# growPi_v2_1.net
KiCad netlist of a schematic drawn in EAGLE
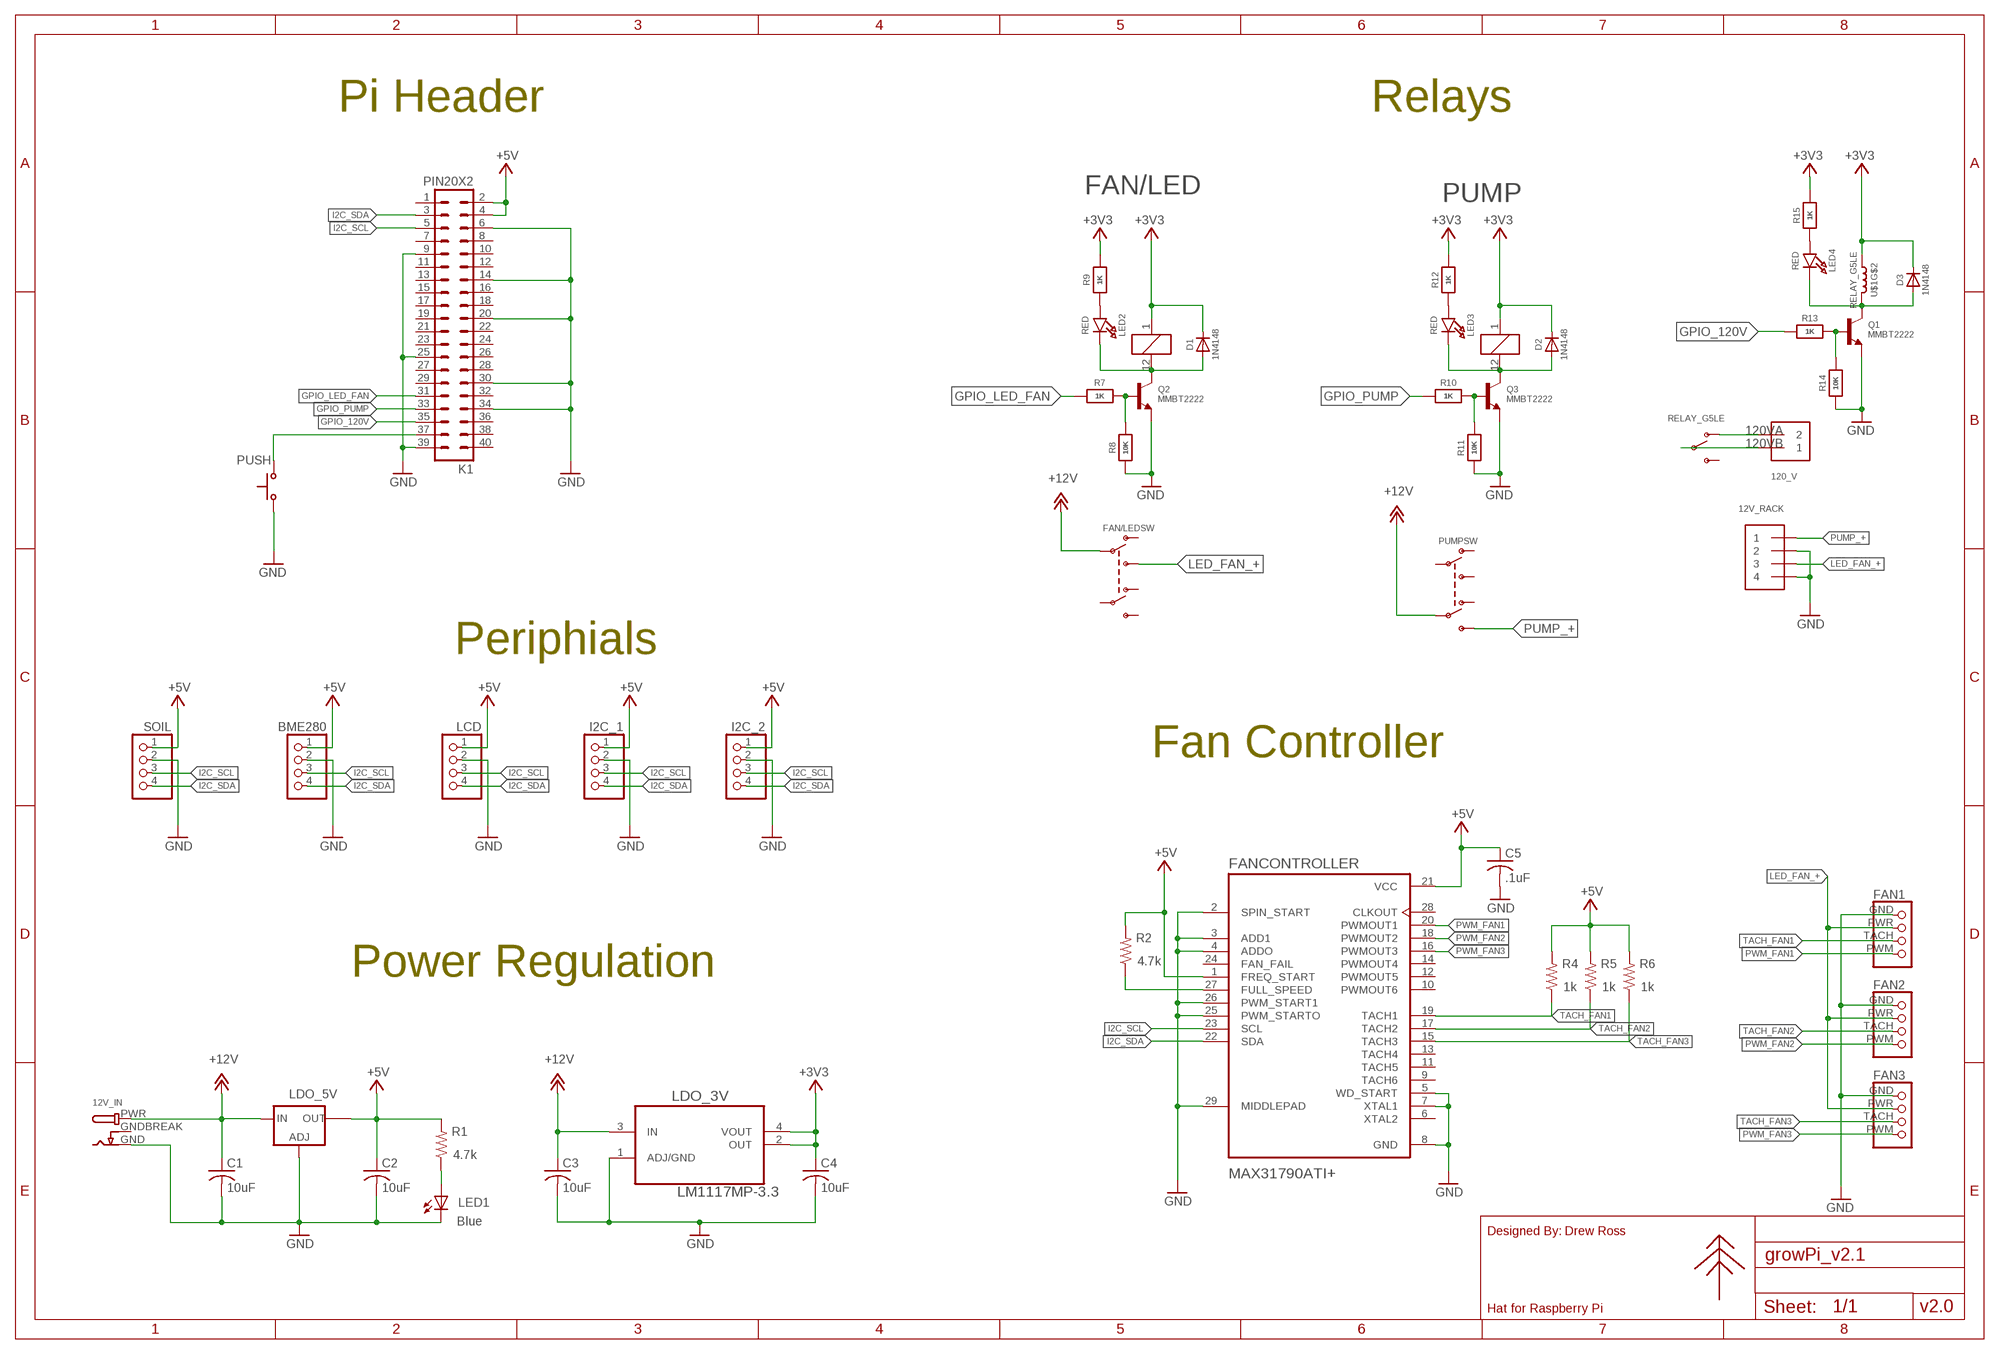
[diagram p0: schematic, sheet 1]

(export (version "E")
  (design (tool "Eeschema 10.0.6"))
  (components
    (comp (ref "12V_IN")
      (value "DCBARRELSMT_CORRECT")
      (footprint "eagle-import:DCJACK_2MM_SMT")
      (libsource (lib "eagle-import") (part "DCBARRELSMT_CORRECT"))
    )
    (comp (ref "12V_RACK")
      (value "TERMBLOCK_1X4-5.0MM")
      (footprint "eagle-import:TERMBLOCK_1X4-5.0MM")
      (libsource (lib "eagle-import") (part "TERMBLOCK_1X4-5.0MM"))
    )
    (comp (ref "120_V")
      (value "TERMBLOCK_1X2-5.0MM")
      (footprint "eagle-import:TERMBLOCK_1X2-5.0MM")
      (libsource (lib "eagle-import") (part "TERMBLOCK_1X2-5.0MM"))
    )
    (comp (ref "BME280")
      (value "PINHD-1X4")
      (footprint "eagle-import:1X04")
      (libsource (lib "eagle-import") (part "PINHD-1X4"))
    )
    (comp (ref "C1")
      (value "10uF")
      (footprint "eagle-import:C0603")
      (libsource (lib "eagle-import") (part "C-USC0603"))
    )
    (comp (ref "C2")
      (value "10uF")
      (footprint "eagle-import:C0603")
      (libsource (lib "eagle-import") (part "C-USC0603"))
    )
    (comp (ref "C3")
      (value "10uF")
      (footprint "eagle-import:C0603")
      (libsource (lib "eagle-import") (part "C-USC0603"))
    )
    (comp (ref "C4")
      (value "10uF")
      (footprint "eagle-import:C0603")
      (libsource (lib "eagle-import") (part "C-USC0603"))
    )
    (comp (ref "C5")
      (value ".1uF")
      (footprint "eagle-import:C0603")
      (libsource (lib "eagle-import") (part "C-USC0603"))
    )
    (comp (ref "D1")
      (value "1N4148")
      (footprint "eagle-import:SOD-323")
      (libsource (lib "eagle-import") (part "DIODESOD-323"))
    )
    (comp (ref "D2")
      (value "1N4148")
      (footprint "eagle-import:SOD-323")
      (libsource (lib "eagle-import") (part "DIODESOD-323"))
    )
    (comp (ref "D3")
      (value "1N4148")
      (footprint "eagle-import:SOD-323")
      (libsource (lib "eagle-import") (part "DIODESOD-323"))
    )
    (comp (ref "FAN/LED")
      (value "RELAY_NONLATCHING-EE2NUH")
      (footprint "eagle-import:RELAY_EE2_NOLATCH")
      (libsource (lib "eagle-import") (part "RELAY_NONLATCHING-EE2NUH"))
    )
    (comp (ref "FAN1")
      (value "4PIN-MOLEX-FAN")
      (footprint "eagle-import:4PIN-FAN-HEADER")
      (libsource (lib "eagle-import") (part "4PIN-MOLEX-FAN"))
    )
    (comp (ref "FAN2")
      (value "4PIN-MOLEX-FAN")
      (footprint "eagle-import:4PIN-FAN-HEADER")
      (libsource (lib "eagle-import") (part "4PIN-MOLEX-FAN"))
    )
    (comp (ref "FAN3")
      (value "4PIN-MOLEX-FAN")
      (footprint "eagle-import:4PIN-FAN-HEADER")
      (libsource (lib "eagle-import") (part "4PIN-MOLEX-FAN"))
    )
    (comp (ref "FANCONTROLLER")
      (value "MAX31790ATI+")
      (footprint "eagle-import:QFN40P400X400X80-29N")
      (fields (field (name "MF") "Maxim Integrated"))
      (libsource (lib "eagle-import") (part "MAX31790ATI+"))
    )
    (comp (ref "I2C_1")
      (value "PINHD-1X4")
      (footprint "eagle-import:1X04")
      (libsource (lib "eagle-import") (part "PINHD-1X4"))
    )
    (comp (ref "I2C_2")
      (value "PINHD-1X4")
      (footprint "eagle-import:1X04")
      (libsource (lib "eagle-import") (part "PINHD-1X4"))
    )
    (comp (ref "K1")
      (value "PIN20X2")
      (footprint "eagle-import:PIN_20X2")
      (libsource (lib "eagle-import") (part "PIN20X2"))
    )
    (comp (ref "LCD")
      (value "PINHD-1X4")
      (footprint "eagle-import:1X04")
      (libsource (lib "eagle-import") (part "PINHD-1X4"))
    )
    (comp (ref "LDO_3V")
      (value "LM1117MP-3.3")
      (footprint "eagle-import:SOT230P696X180-4N")
      (fields (field (name "MF") "Texas Instruments"))
      (libsource (lib "eagle-import") (part "LM1117MP-3.3"))
    )
    (comp (ref "LDO_5V")
      (value "LM1084IS")
      (footprint "eagle-import:TO263")
      (libsource (lib "eagle-import") (part "LM1084IS"))
    )
    (comp (ref "LED1")
      (value "Blue")
      (footprint "eagle-import:CHIPLED_0603")
      (libsource (lib "eagle-import") (part "LEDCHIPLED_0603"))
    )
    (comp (ref "LED2")
      (value "RED")
      (footprint "eagle-import:CHIPLED_0603_NOOUTLINE")
      (libsource (lib "eagle-import") (part "LED0603_NOOUTLINE"))
    )
    (comp (ref "LED3")
      (value "RED")
      (footprint "eagle-import:CHIPLED_0603_NOOUTLINE")
      (libsource (lib "eagle-import") (part "LED0603_NOOUTLINE"))
    )
    (comp (ref "LED4")
      (value "RED")
      (footprint "eagle-import:CHIPLED_0603_NOOUTLINE")
      (libsource (lib "eagle-import") (part "LED0603_NOOUTLINE"))
    )
    (comp (ref "PLANTLOGO")
      (value "PLANTLOGO")
      (footprint "eagle-import:PLANT")
      (libsource (lib "eagle-import") (part "PLANTLOGO"))
    )
    (comp (ref "PUMP")
      (value "RELAY_NONLATCHING-EE2NUH")
      (footprint "eagle-import:RELAY_EE2_NOLATCH")
      (libsource (lib "eagle-import") (part "RELAY_NONLATCHING-EE2NUH"))
    )
    (comp (ref "PUSH")
      (value "PTS645SSMTR")
      (footprint "eagle-import:PTS645-SMD")
      (libsource (lib "eagle-import") (part "PTS645S???SMTR"))
    )
    (comp (ref "Q1")
      (value "MMBT2222")
      (footprint "eagle-import:SOT23-R")
      (libsource (lib "eagle-import") (part "TRANSISTOR_NPN"))
    )
    (comp (ref "Q2")
      (value "MMBT2222")
      (footprint "eagle-import:SOT23-R")
      (libsource (lib "eagle-import") (part "TRANSISTOR_NPN"))
    )
    (comp (ref "Q3")
      (value "MMBT2222")
      (footprint "eagle-import:SOT23-R")
      (libsource (lib "eagle-import") (part "TRANSISTOR_NPN"))
    )
    (comp (ref "R1")
      (value "4.7k")
      (footprint "eagle-import:R0603")
      (libsource (lib "eagle-import") (part "R-US_R0603"))
    )
    (comp (ref "R2")
      (value "4.7k")
      (footprint "eagle-import:R0603")
      (libsource (lib "eagle-import") (part "R-US_R0603"))
    )
    (comp (ref "R4")
      (value "1k")
      (footprint "eagle-import:R0603")
      (libsource (lib "eagle-import") (part "R-US_R0603"))
    )
    (comp (ref "R5")
      (value "1k")
      (footprint "eagle-import:R0603")
      (libsource (lib "eagle-import") (part "R-US_R0603"))
    )
    (comp (ref "R6")
      (value "1k")
      (footprint "eagle-import:R0603")
      (libsource (lib "eagle-import") (part "R-US_R0603"))
    )
    (comp (ref "R7")
      (value "1K")
      (footprint "eagle-import:0603-NO")
      (libsource (lib "eagle-import") (part "RESISTOR_0603_NOOUT"))
    )
    (comp (ref "R8")
      (value "10K")
      (footprint "eagle-import:0603-NO")
      (libsource (lib "eagle-import") (part "RESISTOR_0603_NOOUT"))
    )
    (comp (ref "R9")
      (value "1K")
      (footprint "eagle-import:0603-NO")
      (libsource (lib "eagle-import") (part "RESISTOR_0603_NOOUT"))
    )
    (comp (ref "R10")
      (value "1K")
      (footprint "eagle-import:0603-NO")
      (libsource (lib "eagle-import") (part "RESISTOR_0603_NOOUT"))
    )
    (comp (ref "R11")
      (value "10K")
      (footprint "eagle-import:0603-NO")
      (libsource (lib "eagle-import") (part "RESISTOR_0603_NOOUT"))
    )
    (comp (ref "R12")
      (value "1K")
      (footprint "eagle-import:0603-NO")
      (libsource (lib "eagle-import") (part "RESISTOR_0603_NOOUT"))
    )
    (comp (ref "R13")
      (value "1K")
      (footprint "eagle-import:0603-NO")
      (libsource (lib "eagle-import") (part "RESISTOR_0603_NOOUT"))
    )
    (comp (ref "R14")
      (value "10K")
      (footprint "eagle-import:0603-NO")
      (libsource (lib "eagle-import") (part "RESISTOR_0603_NOOUT"))
    )
    (comp (ref "R15")
      (value "1K")
      (footprint "eagle-import:0603-NO")
      (libsource (lib "eagle-import") (part "RESISTOR_0603_NOOUT"))
    )
    (comp (ref "SOIL")
      (value "PINHD-1X4")
      (footprint "eagle-import:1X04")
      (libsource (lib "eagle-import") (part "PINHD-1X4"))
    )
    (comp (ref "U$1")
      (value "RELAY_G5LE")
      (footprint "eagle-import:RELAY_G5LE-1")
      (libsource (lib "eagle-import") (part "RELAY_G5LE"))
    )
  )
  (nets
    (net (code "1") (name "+3V3") (class "Default")
      (node (ref "C4") (pin "1") (pinfunction "1_1") (pintype "passive"))
      (node (ref "D1") (pin "C") (pinfunction "C_C") (pintype "passive"))
      (node (ref "D2") (pin "C") (pinfunction "C_C") (pintype "passive"))
      (node (ref "D3") (pin "C") (pinfunction "C_C") (pintype "passive"))
      (node (ref "FAN/LED") (pin "1") (pinfunction "1_1") (pintype "passive"))
      (node (ref "LDO_3V") (pin "2") (pinfunction "OUT_2") (pintype "output"))
      (node (ref "LDO_3V") (pin "4") (pinfunction "VOUT_4") (pintype "output"))
      (node (ref "PUMP") (pin "1") (pinfunction "1_1") (pintype "passive"))
      (node (ref "R12") (pin "2") (pinfunction "2_2") (pintype "passive"))
      (node (ref "R15") (pin "2") (pinfunction "2_2") (pintype "passive"))
      (node (ref "R9") (pin "2") (pinfunction "2_2") (pintype "passive"))
      (node (ref "U$1") (pin "2") (pinfunction "1_2") (pintype "passive"))
    )
    (net (code "2") (name "+5V") (class "Default")
      (node (ref "BME280") (pin "1") (pinfunction "1_1") (pintype "passive"))
      (node (ref "C2") (pin "1") (pinfunction "1_1") (pintype "passive"))
      (node (ref "C5") (pin "1") (pinfunction "1_1") (pintype "passive"))
      (node (ref "FANCONTROLLER") (pin "1") (pinfunction "FREQ_START_1") (pintype "bidirectional"))
      (node (ref "FANCONTROLLER") (pin "21") (pinfunction "VCC_21") (pintype "power_in"))
      (node (ref "I2C_1") (pin "1") (pinfunction "1_1") (pintype "passive"))
      (node (ref "I2C_2") (pin "1") (pinfunction "1_1") (pintype "passive"))
      (node (ref "K1") (pin "2") (pinfunction "2_2") (pintype "passive"))
      (node (ref "K1") (pin "4") (pinfunction "4_4") (pintype "passive"))
      (node (ref "LCD") (pin "1") (pinfunction "1_1") (pintype "passive"))
      (node (ref "LDO_5V") (pin "2") (pinfunction "OUT_2") (pintype "passive"))
      (node (ref "R1") (pin "2") (pinfunction "2_2") (pintype "passive"))
      (node (ref "R2") (pin "2") (pinfunction "2_2") (pintype "passive"))
      (node (ref "R4") (pin "2") (pinfunction "2_2") (pintype "passive"))
      (node (ref "R5") (pin "2") (pinfunction "2_2") (pintype "passive"))
      (node (ref "R6") (pin "2") (pinfunction "2_2") (pintype "passive"))
      (node (ref "SOIL") (pin "1") (pinfunction "1_1") (pintype "passive"))
    )
    (net (code "3") (name "+12V") (class "Default")
      (node (ref "12V_IN") (pin "PWR") (pinfunction "PWR_PWR") (pintype "power_in"))
      (node (ref "C1") (pin "1") (pinfunction "1_1") (pintype "passive"))
      (node (ref "C3") (pin "1") (pinfunction "1_1") (pintype "passive"))
      (node (ref "FAN/LED") (pin "9") (pinfunction "P1_9") (pintype "passive"))
      (node (ref "LDO_3V") (pin "3") (pinfunction "IN_3") (pintype "input"))
      (node (ref "LDO_5V") (pin "3") (pinfunction "IN_3") (pintype "input"))
      (node (ref "PUMP") (pin "4") (pinfunction "P2_4") (pintype "passive"))
    )
    (net (code "4") (name "/120VA") (class "Default")
      (node (ref "120_V") (pin "2") (pinfunction "2_2") (pintype "passive"))
      (node (ref "U$1") (pin "3") (pinfunction "O_3") (pintype "passive"))
    )
    (net (code "5") (name "/120VB") (class "Default")
      (node (ref "120_V") (pin "1") (pinfunction "1_1") (pintype "passive"))
      (node (ref "U$1") (pin "1") (pinfunction "P_1") (pintype "passive"))
    )
    (net (code "6") (name "/GNDBREAK") (class "Default")
      (node (ref "12V_IN") (pin "GNDBREAK") (pinfunction "GNDBREAK_GNDBREAK") (pintype "power_in"))
    )
    (net (code "7") (name "GND") (class "Default")
      (node (ref "12V_IN") (pin "GND") (pinfunction "GND_GND") (pintype "power_in"))
      (node (ref "12V_RACK") (pin "2") (pinfunction "2_2") (pintype "passive"))
      (node (ref "12V_RACK") (pin "4") (pinfunction "4_4") (pintype "passive"))
      (node (ref "BME280") (pin "2") (pinfunction "2_2") (pintype "passive"))
      (node (ref "C1") (pin "2") (pinfunction "2_2") (pintype "passive"))
      (node (ref "C2") (pin "2") (pinfunction "2_2") (pintype "passive"))
      (node (ref "C3") (pin "2") (pinfunction "2_2") (pintype "passive"))
      (node (ref "C4") (pin "2") (pinfunction "2_2") (pintype "passive"))
      (node (ref "C5") (pin "2") (pinfunction "2_2") (pintype "passive"))
      (node (ref "FAN1") (pin "GND") (pinfunction "1_GND") (pintype "passive"))
      (node (ref "FAN2") (pin "GND") (pinfunction "1_GND") (pintype "passive"))
      (node (ref "FAN3") (pin "GND") (pinfunction "1_GND") (pintype "passive"))
      (node (ref "FANCONTROLLER") (pin "2") (pinfunction "SPIN_START_2") (pintype "input"))
      (node (ref "FANCONTROLLER") (pin "25") (pinfunction "PWM_STARTO_25") (pintype "bidirectional"))
      (node (ref "FANCONTROLLER") (pin "26") (pinfunction "PWM_START1_26") (pintype "bidirectional"))
      (node (ref "FANCONTROLLER") (pin "29") (pinfunction "MIDDLEPAD_29") (pintype "bidirectional"))
      (node (ref "FANCONTROLLER") (pin "3") (pinfunction "ADD1_3") (pintype "bidirectional"))
      (node (ref "FANCONTROLLER") (pin "4") (pinfunction "ADDO_4") (pintype "bidirectional"))
      (node (ref "FANCONTROLLER") (pin "5") (pinfunction "WD_START_5") (pintype "bidirectional"))
      (node (ref "FANCONTROLLER") (pin "7") (pinfunction "XTAL1_7") (pintype "bidirectional"))
      (node (ref "FANCONTROLLER") (pin "8") (pinfunction "GND_8") (pintype "power_in"))
      (node (ref "I2C_1") (pin "2") (pinfunction "2_2") (pintype "passive"))
      (node (ref "I2C_2") (pin "2") (pinfunction "2_2") (pintype "passive"))
      (node (ref "K1") (pin "14") (pinfunction "14_14") (pintype "passive"))
      (node (ref "K1") (pin "20") (pinfunction "20_20") (pintype "passive"))
      (node (ref "K1") (pin "25") (pinfunction "25_25") (pintype "passive"))
      (node (ref "K1") (pin "30") (pinfunction "30_30") (pintype "passive"))
      (node (ref "K1") (pin "34") (pinfunction "34_34") (pintype "passive"))
      (node (ref "K1") (pin "39") (pinfunction "39_39") (pintype "passive"))
      (node (ref "K1") (pin "6") (pinfunction "6_6") (pintype "passive"))
      (node (ref "K1") (pin "9") (pinfunction "9_9") (pintype "passive"))
      (node (ref "LCD") (pin "2") (pinfunction "2_2") (pintype "passive"))
      (node (ref "LDO_3V") (pin "1") (pinfunction "ADJ/GND_1") (pintype "passive"))
      (node (ref "LDO_5V") (pin "1") (pinfunction "ADJ_1") (pintype "input"))
      (node (ref "LED1") (pin "C") (pinfunction "C_C") (pintype "passive"))
      (node (ref "PUSH") (pin "1") (pinfunction "P_1") (pintype "passive"))
      (node (ref "PUSH") (pin "2") (pinfunction "P_2") (pintype "passive"))
      (node (ref "Q1") (pin "2") (pinfunction "E_2") (pintype "passive"))
      (node (ref "Q2") (pin "2") (pinfunction "E_2") (pintype "passive"))
      (node (ref "Q3") (pin "2") (pinfunction "E_2") (pintype "passive"))
      (node (ref "R11") (pin "1") (pinfunction "1_1") (pintype "passive"))
      (node (ref "R14") (pin "1") (pinfunction "1_1") (pintype "passive"))
      (node (ref "R8") (pin "1") (pinfunction "1_1") (pintype "passive"))
      (node (ref "SOIL") (pin "2") (pinfunction "2_2") (pintype "passive"))
    )
    (net (code "8") (name "GPIO_120V") (class "Default")
      (node (ref "K1") (pin "35") (pinfunction "35_35") (pintype "passive"))
      (node (ref "R13") (pin "1") (pinfunction "1_1") (pintype "passive"))
    )
    (net (code "9") (name "GPIO_LED_FAN") (class "Default")
      (node (ref "K1") (pin "31") (pinfunction "31_31") (pintype "passive"))
      (node (ref "R7") (pin "1") (pinfunction "1_1") (pintype "passive"))
    )
    (net (code "10") (name "GPIO_PUMP") (class "Default")
      (node (ref "K1") (pin "33") (pinfunction "33_33") (pintype "passive"))
      (node (ref "R10") (pin "1") (pinfunction "1_1") (pintype "passive"))
    )
    (net (code "11") (name "I2C_SCL") (class "Default")
      (node (ref "BME280") (pin "3") (pinfunction "3_3") (pintype "passive"))
      (node (ref "FANCONTROLLER") (pin "23") (pinfunction "SCL_23") (pintype "bidirectional"))
      (node (ref "I2C_1") (pin "3") (pinfunction "3_3") (pintype "passive"))
      (node (ref "I2C_2") (pin "3") (pinfunction "3_3") (pintype "passive"))
      (node (ref "K1") (pin "5") (pinfunction "5_5") (pintype "passive"))
      (node (ref "LCD") (pin "3") (pinfunction "3_3") (pintype "passive"))
      (node (ref "SOIL") (pin "3") (pinfunction "3_3") (pintype "passive"))
    )
    (net (code "12") (name "I2C_SDA") (class "Default")
      (node (ref "BME280") (pin "4") (pinfunction "4_4") (pintype "passive"))
      (node (ref "FANCONTROLLER") (pin "22") (pinfunction "SDA_22") (pintype "bidirectional"))
      (node (ref "I2C_1") (pin "4") (pinfunction "4_4") (pintype "passive"))
      (node (ref "I2C_2") (pin "4") (pinfunction "4_4") (pintype "passive"))
      (node (ref "K1") (pin "3") (pinfunction "3_3") (pintype "passive"))
      (node (ref "LCD") (pin "4") (pinfunction "4_4") (pintype "passive"))
      (node (ref "SOIL") (pin "4") (pinfunction "4_4") (pintype "passive"))
    )
    (net (code "13") (name "LED_FAN_+") (class "Default")
      (node (ref "12V_RACK") (pin "3") (pinfunction "3_3") (pintype "passive"))
      (node (ref "FAN/LED") (pin "8") (pinfunction "S1_8") (pintype "passive"))
      (node (ref "FAN1") (pin "PWR") (pinfunction "2_PWR") (pintype "passive"))
      (node (ref "FAN2") (pin "PWR") (pinfunction "2_PWR") (pintype "passive"))
      (node (ref "FAN3") (pin "PWR") (pinfunction "2_PWR") (pintype "passive"))
    )
    (net (code "14") (name "Net-(FAN/LEDA-2)") (class "Default")
      (node (ref "D1") (pin "A") (pinfunction "A_A") (pintype "passive"))
      (node (ref "FAN/LED") (pin "12") (pinfunction "2_12") (pintype "passive"))
      (node (ref "LED2") (pin "C") (pinfunction "C_C") (pintype "passive"))
      (node (ref "Q2") (pin "3") (pinfunction "C_3") (pintype "passive"))
    )
    (net (code "15") (name "Net-(FANCONTROLLER-FULL_SPEED)") (class "Default")
      (node (ref "FANCONTROLLER") (pin "27") (pinfunction "FULL_SPEED_27") (pintype "bidirectional"))
      (node (ref "R2") (pin "1") (pinfunction "1_1") (pintype "passive"))
    )
    (net (code "16") (name "Net-(K1-Pad37)") (class "Default")
      (node (ref "K1") (pin "37") (pinfunction "37_37") (pintype "passive"))
      (node (ref "PUSH") (pin "3") (pinfunction "S_3") (pintype "passive"))
      (node (ref "PUSH") (pin "4") (pinfunction "S_4") (pintype "passive"))
    )
    (net (code "17") (name "Net-(LED1-PadA)") (class "Default")
      (node (ref "LED1") (pin "A") (pinfunction "A_A") (pintype "passive"))
      (node (ref "R1") (pin "1") (pinfunction "1_1") (pintype "passive"))
    )
    (net (code "18") (name "Net-(LED2-PadA)") (class "Default")
      (node (ref "LED2") (pin "A") (pinfunction "A_A") (pintype "passive"))
      (node (ref "R9") (pin "1") (pinfunction "1_1") (pintype "passive"))
    )
    (net (code "19") (name "Net-(LED3-PadA)") (class "Default")
      (node (ref "LED3") (pin "A") (pinfunction "A_A") (pintype "passive"))
      (node (ref "R12") (pin "1") (pinfunction "1_1") (pintype "passive"))
    )
    (net (code "20") (name "Net-(LED4-PadA)") (class "Default")
      (node (ref "LED4") (pin "A") (pinfunction "A_A") (pintype "passive"))
      (node (ref "R15") (pin "1") (pinfunction "1_1") (pintype "passive"))
    )
    (net (code "21") (name "Net-(PUMPA-2)") (class "Default")
      (node (ref "D2") (pin "A") (pinfunction "A_A") (pintype "passive"))
      (node (ref "LED3") (pin "C") (pinfunction "C_C") (pintype "passive"))
      (node (ref "PUMP") (pin "12") (pinfunction "2_12") (pintype "passive"))
      (node (ref "Q3") (pin "3") (pinfunction "C_3") (pintype "passive"))
    )
    (net (code "22") (name "Net-(Q1-B)") (class "Default")
      (node (ref "Q1") (pin "1") (pinfunction "B_1") (pintype "passive"))
      (node (ref "R13") (pin "2") (pinfunction "2_2") (pintype "passive"))
      (node (ref "R14") (pin "2") (pinfunction "2_2") (pintype "passive"))
    )
    (net (code "23") (name "Net-(Q1-C)") (class "Default")
      (node (ref "D3") (pin "A") (pinfunction "A_A") (pintype "passive"))
      (node (ref "LED4") (pin "C") (pinfunction "C_C") (pintype "passive"))
      (node (ref "Q1") (pin "3") (pinfunction "C_3") (pintype "passive"))
      (node (ref "U$1") (pin "5") (pinfunction "2_5") (pintype "passive"))
    )
    (net (code "24") (name "Net-(Q2-B)") (class "Default")
      (node (ref "Q2") (pin "1") (pinfunction "B_1") (pintype "passive"))
      (node (ref "R7") (pin "2") (pinfunction "2_2") (pintype "passive"))
      (node (ref "R8") (pin "2") (pinfunction "2_2") (pintype "passive"))
    )
    (net (code "25") (name "Net-(Q3-B)") (class "Default")
      (node (ref "Q3") (pin "1") (pinfunction "B_1") (pintype "passive"))
      (node (ref "R10") (pin "2") (pinfunction "2_2") (pintype "passive"))
      (node (ref "R11") (pin "2") (pinfunction "2_2") (pintype "passive"))
    )
    (net (code "26") (name "PUMP_+") (class "Default")
      (node (ref "12V_RACK") (pin "1") (pinfunction "1_1") (pintype "passive"))
      (node (ref "PUMP") (pin "5") (pinfunction "S2_5") (pintype "passive"))
    )
    (net (code "27") (name "PWM_FAN1") (class "Default")
      (node (ref "FAN1") (pin "PWM") (pinfunction "4_PWM") (pintype "passive"))
      (node (ref "FANCONTROLLER") (pin "20") (pinfunction "PWMOUT1_20") (pintype "output"))
    )
    (net (code "28") (name "PWM_FAN2") (class "Default")
      (node (ref "FAN2") (pin "PWM") (pinfunction "4_PWM") (pintype "passive"))
      (node (ref "FANCONTROLLER") (pin "18") (pinfunction "PWMOUT2_18") (pintype "output"))
    )
    (net (code "29") (name "PWM_FAN3") (class "Default")
      (node (ref "FAN3") (pin "PWM") (pinfunction "4_PWM") (pintype "passive"))
      (node (ref "FANCONTROLLER") (pin "16") (pinfunction "PWMOUT3_16") (pintype "output"))
    )
    (net (code "30") (name "TACH_FAN1") (class "Default")
      (node (ref "FAN1") (pin "TACH") (pinfunction "3_TACH") (pintype "passive"))
      (node (ref "FANCONTROLLER") (pin "19") (pinfunction "TACH1_19") (pintype "bidirectional"))
      (node (ref "R4") (pin "1") (pinfunction "1_1") (pintype "passive"))
    )
    (net (code "31") (name "TACH_FAN2") (class "Default")
      (node (ref "FAN2") (pin "TACH") (pinfunction "3_TACH") (pintype "passive"))
      (node (ref "FANCONTROLLER") (pin "17") (pinfunction "TACH2_17") (pintype "bidirectional"))
      (node (ref "R5") (pin "1") (pinfunction "1_1") (pintype "passive"))
    )
    (net (code "32") (name "TACH_FAN3") (class "Default")
      (node (ref "FAN3") (pin "TACH") (pinfunction "3_TACH") (pintype "passive"))
      (node (ref "FANCONTROLLER") (pin "15") (pinfunction "TACH3_15") (pintype "bidirectional"))
      (node (ref "R6") (pin "1") (pinfunction "1_1") (pintype "passive"))
    )
    (net (code "33") (name "unconnected-(FAN/LEDB-O1-Pad10)") (class "Default")
      (node (ref "FAN/LED") (pin "10") (pinfunction "O1_10") (pintype "passive"))
    )
    (net (code "34") (name "unconnected-(FAN/LEDB-O2-Pad3)") (class "Default")
      (node (ref "FAN/LED") (pin "3") (pinfunction "O2_3") (pintype "passive"))
    )
    (net (code "35") (name "unconnected-(FAN/LEDB-P2-Pad4)") (class "Default")
      (node (ref "FAN/LED") (pin "4") (pinfunction "P2_4") (pintype "passive"))
    )
    (net (code "36") (name "unconnected-(FAN/LEDB-S2-Pad5)") (class "Default")
      (node (ref "FAN/LED") (pin "5") (pinfunction "S2_5") (pintype "passive"))
    )
    (net (code "37") (name "unconnected-(FANCONTROLLER-CLKOUT-Pad28)") (class "Default")
      (node (ref "FANCONTROLLER") (pin "28") (pinfunction "CLKOUT_28") (pintype "output"))
    )
    (net (code "38") (name "unconnected-(FANCONTROLLER-FAN_FAIL-Pad24)") (class "Default")
      (node (ref "FANCONTROLLER") (pin "24") (pinfunction "FAN_FAIL_24") (pintype "bidirectional"))
    )
    (net (code "39") (name "unconnected-(FANCONTROLLER-PWMOUT4-Pad14)") (class "Default")
      (node (ref "FANCONTROLLER") (pin "14") (pinfunction "PWMOUT4_14") (pintype "output"))
    )
    (net (code "40") (name "unconnected-(FANCONTROLLER-PWMOUT5-Pad12)") (class "Default")
      (node (ref "FANCONTROLLER") (pin "12") (pinfunction "PWMOUT5_12") (pintype "output"))
    )
    (net (code "41") (name "unconnected-(FANCONTROLLER-PWMOUT6-Pad10)") (class "Default")
      (node (ref "FANCONTROLLER") (pin "10") (pinfunction "PWMOUT6_10") (pintype "output"))
    )
    (net (code "42") (name "unconnected-(FANCONTROLLER-TACH4-Pad13)") (class "Default")
      (node (ref "FANCONTROLLER") (pin "13") (pinfunction "TACH4_13") (pintype "bidirectional"))
    )
    (net (code "43") (name "unconnected-(FANCONTROLLER-TACH5-Pad11)") (class "Default")
      (node (ref "FANCONTROLLER") (pin "11") (pinfunction "TACH5_11") (pintype "bidirectional"))
    )
    (net (code "44") (name "unconnected-(FANCONTROLLER-TACH6-Pad9)") (class "Default")
      (node (ref "FANCONTROLLER") (pin "9") (pinfunction "TACH6_9") (pintype "bidirectional"))
    )
    (net (code "45") (name "unconnected-(FANCONTROLLER-XTAL2-Pad6)") (class "Default")
      (node (ref "FANCONTROLLER") (pin "6") (pinfunction "XTAL2_6") (pintype "bidirectional"))
    )
    (net (code "46") (name "unconnected-(K1-Pad1)") (class "Default")
      (node (ref "K1") (pin "1") (pinfunction "1_1") (pintype "passive"))
    )
    (net (code "47") (name "unconnected-(K1-Pad7)") (class "Default")
      (node (ref "K1") (pin "7") (pinfunction "7_7") (pintype "passive"))
    )
    (net (code "48") (name "unconnected-(K1-Pad8)") (class "Default")
      (node (ref "K1") (pin "8") (pinfunction "8_8") (pintype "passive"))
    )
    (net (code "49") (name "unconnected-(K1-Pad10)") (class "Default")
      (node (ref "K1") (pin "10") (pinfunction "10_10") (pintype "passive"))
    )
    (net (code "50") (name "unconnected-(K1-Pad11)") (class "Default")
      (node (ref "K1") (pin "11") (pinfunction "11_11") (pintype "passive"))
    )
    (net (code "51") (name "unconnected-(K1-Pad12)") (class "Default")
      (node (ref "K1") (pin "12") (pinfunction "12_12") (pintype "passive"))
    )
    (net (code "52") (name "unconnected-(K1-Pad13)") (class "Default")
      (node (ref "K1") (pin "13") (pinfunction "13_13") (pintype "passive"))
    )
    (net (code "53") (name "unconnected-(K1-Pad15)") (class "Default")
      (node (ref "K1") (pin "15") (pinfunction "15_15") (pintype "passive"))
    )
    (net (code "54") (name "unconnected-(K1-Pad16)") (class "Default")
      (node (ref "K1") (pin "16") (pinfunction "16_16") (pintype "passive"))
    )
    (net (code "55") (name "unconnected-(K1-Pad17)") (class "Default")
      (node (ref "K1") (pin "17") (pinfunction "17_17") (pintype "passive"))
    )
    (net (code "56") (name "unconnected-(K1-Pad18)") (class "Default")
      (node (ref "K1") (pin "18") (pinfunction "18_18") (pintype "passive"))
    )
    (net (code "57") (name "unconnected-(K1-Pad19)") (class "Default")
      (node (ref "K1") (pin "19") (pinfunction "19_19") (pintype "passive"))
    )
    (net (code "58") (name "unconnected-(K1-Pad21)") (class "Default")
      (node (ref "K1") (pin "21") (pinfunction "21_21") (pintype "passive"))
    )
    (net (code "59") (name "unconnected-(K1-Pad22)") (class "Default")
      (node (ref "K1") (pin "22") (pinfunction "22_22") (pintype "passive"))
    )
    (net (code "60") (name "unconnected-(K1-Pad23)") (class "Default")
      (node (ref "K1") (pin "23") (pinfunction "23_23") (pintype "passive"))
    )
    (net (code "61") (name "unconnected-(K1-Pad24)") (class "Default")
      (node (ref "K1") (pin "24") (pinfunction "24_24") (pintype "passive"))
    )
    (net (code "62") (name "unconnected-(K1-Pad26)") (class "Default")
      (node (ref "K1") (pin "26") (pinfunction "26_26") (pintype "passive"))
    )
    (net (code "63") (name "unconnected-(K1-Pad27)") (class "Default")
      (node (ref "K1") (pin "27") (pinfunction "27_27") (pintype "passive"))
    )
    (net (code "64") (name "unconnected-(K1-Pad28)") (class "Default")
      (node (ref "K1") (pin "28") (pinfunction "28_28") (pintype "passive"))
    )
    (net (code "65") (name "unconnected-(K1-Pad29)") (class "Default")
      (node (ref "K1") (pin "29") (pinfunction "29_29") (pintype "passive"))
    )
    (net (code "66") (name "unconnected-(K1-Pad32)") (class "Default")
      (node (ref "K1") (pin "32") (pinfunction "32_32") (pintype "passive"))
    )
    (net (code "67") (name "unconnected-(K1-Pad36)") (class "Default")
      (node (ref "K1") (pin "36") (pinfunction "36_36") (pintype "passive"))
    )
    (net (code "68") (name "unconnected-(K1-Pad38)") (class "Default")
      (node (ref "K1") (pin "38") (pinfunction "38_38") (pintype "passive"))
    )
    (net (code "69") (name "unconnected-(K1-Pad40)") (class "Default")
      (node (ref "K1") (pin "40") (pinfunction "40_40") (pintype "passive"))
    )
    (net (code "70") (name "unconnected-(LDO_5V-OUT4-Pad4)") (class "Default")
      (node (ref "LDO_5V") (pin "4") (pinfunction "OUT4_4") (pintype "passive"))
    )
    (net (code "71") (name "unconnected-(PUMPB-O1-Pad10)") (class "Default")
      (node (ref "PUMP") (pin "10") (pinfunction "O1_10") (pintype "passive"))
    )
    (net (code "72") (name "unconnected-(PUMPB-O2-Pad3)") (class "Default")
      (node (ref "PUMP") (pin "3") (pinfunction "O2_3") (pintype "passive"))
    )
    (net (code "73") (name "unconnected-(PUMPB-P1-Pad9)") (class "Default")
      (node (ref "PUMP") (pin "9") (pinfunction "P1_9") (pintype "passive"))
    )
    (net (code "74") (name "unconnected-(PUMPB-S1-Pad8)") (class "Default")
      (node (ref "PUMP") (pin "8") (pinfunction "S1_8") (pintype "passive"))
    )
    (net (code "75") (name "unconnected-(U$1A-S-Pad4)") (class "Default")
      (node (ref "U$1") (pin "4") (pinfunction "S_4") (pintype "passive"))
    )
  )
)
